# TNY-Test.net
KiCad netlist of a schematic drawn in EAGLE
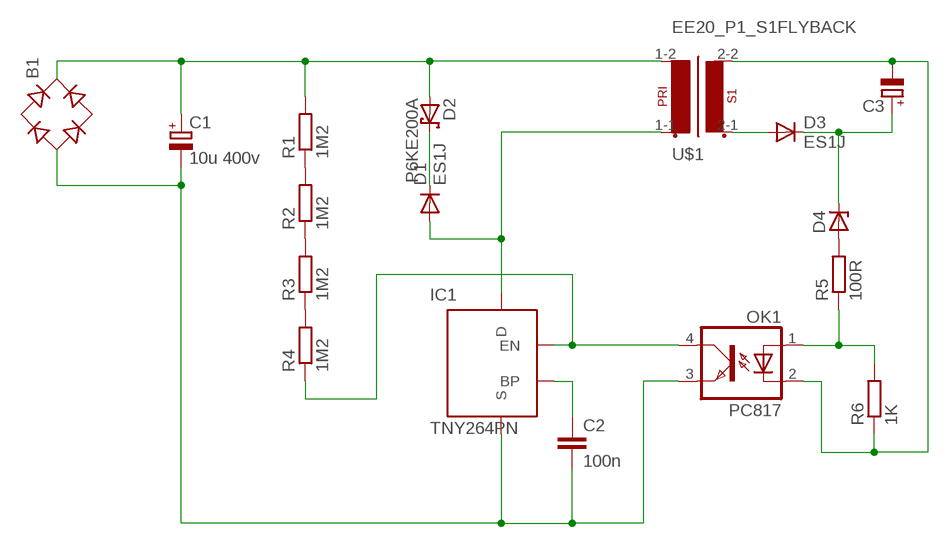
[diagram p0: schematic, sheet 1]

(export (version "E")
  (design (tool "Eeschema 10.0.6"))
  (components
    (comp (ref "B1")
      (value "RB1A")
      (footprint "eagle-import:RB1A")
      (libsource (lib "eagle-import") (part "RB1A"))
    )
    (comp (ref "C1")
      (value "10u 400v")
      (footprint "eagle-import:E5-13")
      (libsource (lib "eagle-import") (part "CPOL-EUE5-13"))
    )
    (comp (ref "C2")
      (value "100n")
      (footprint "eagle-import:C0805")
      (libsource (lib "eagle-import") (part "C-EUC0805"))
    )
    (comp (ref "C3")
      (value "CPOL-EUE2.5-7")
      (footprint "eagle-import:E2,5-7")
      (libsource (lib "eagle-import") (part "CPOL-EUE2.5-7"))
    )
    (comp (ref "D1")
      (value "ES1J")
      (footprint "eagle-import:DO214AC")
      (libsource (lib "eagle-import") (part "DIODE-DO214AC"))
    )
    (comp (ref "D2")
      (value "P6KE200A")
      (footprint "eagle-import:CB417-15")
      (libsource (lib "eagle-import") (part "P6KEXX"))
    )
    (comp (ref "D3")
      (value "ES1J")
      (footprint "eagle-import:DO214AC")
      (libsource (lib "eagle-import") (part "DIODE-DO214AC"))
    )
    (comp (ref "D4")
      (value "ZENER-DIODEDO41Z10")
      (footprint "eagle-import:DO41Z10")
      (libsource (lib "eagle-import") (part "ZENER-DIODEDO41Z10"))
    )
    (comp (ref "IC1")
      (value "TNY264PN")
      (footprint "eagle-import:DIP-8B")
      (libsource (lib "eagle-import") (part "TNY264PN"))
    )
    (comp (ref "OK1")
      (value "PC817")
      (footprint "eagle-import:DIL04")
      (fields (field (name "MPN") "PC817X4J000F"))
      (libsource (lib "eagle-import") (part "PC817"))
    )
    (comp (ref "R1")
      (value "1M2")
      (footprint "eagle-import:R0805")
      (libsource (lib "eagle-import") (part "R-EU_R0805"))
    )
    (comp (ref "R2")
      (value "1M2")
      (footprint "eagle-import:R0805")
      (libsource (lib "eagle-import") (part "R-EU_R0805"))
    )
    (comp (ref "R3")
      (value "1M2")
      (footprint "eagle-import:R0805")
      (libsource (lib "eagle-import") (part "R-EU_R0805"))
    )
    (comp (ref "R4")
      (value "1M2")
      (footprint "eagle-import:R0805")
      (libsource (lib "eagle-import") (part "R-EU_R0805"))
    )
    (comp (ref "R5")
      (value "100R")
      (footprint "eagle-import:R0805")
      (libsource (lib "eagle-import") (part "R-EU_R0805"))
    )
    (comp (ref "R6")
      (value "1K")
      (footprint "eagle-import:R0805")
      (libsource (lib "eagle-import") (part "R-EU_R0805"))
    )
    (comp (ref "U$1")
      (value "EE20_P1_S1FLYBACK")
      (footprint "eagle-import:EE20_P1_S1-REV-4PIN")
      (libsource (lib "eagle-import") (part "EE20_P1_S1FLYBACK"))
    )
  )
  (nets
    (net (code "1") (name "Net-(C3-Pad+)") (class "Default")
      (node (ref "C3") (pin "+") (pinfunction "+_+") (pintype "passive"))
      (node (ref "D3") (pin "C") (pinfunction "C_C") (pintype "passive"))
      (node (ref "D4") (pin "C") (pinfunction "C_C") (pintype "passive"))
    )
    (net (code "2") (name "Net-(D1-PadC)") (class "Default")
      (node (ref "D1") (pin "C") (pinfunction "C_C") (pintype "passive"))
      (node (ref "D2") (pin "C") (pinfunction "C_C") (pintype "passive"))
    )
    (net (code "3") (name "Net-(D4-PadA)") (class "Default")
      (node (ref "D4") (pin "A") (pinfunction "A_A") (pintype "passive"))
      (node (ref "R5") (pin "2") (pinfunction "2_2") (pintype "passive"))
    )
    (net (code "4") (name "Net-(IC1-BP)") (class "Default")
      (node (ref "C2") (pin "1") (pinfunction "1_1") (pintype "passive"))
      (node (ref "IC1") (pin "1") (pinfunction "BP_1") (pintype "input"))
    )
    (net (code "5") (name "Net-(IC1-D)") (class "Default")
      (node (ref "D1") (pin "A") (pinfunction "A_A") (pintype "passive"))
      (node (ref "IC1") (pin "5") (pinfunction "D_5") (pintype "input"))
      (node (ref "U$1") (pin "1-1") (pinfunction "P1-1_1-1") (pintype "passive"))
    )
    (net (code "6") (name "Net-(IC1-EN)") (class "Default")
      (node (ref "IC1") (pin "4") (pinfunction "EN_4") (pintype "input"))
      (node (ref "OK1") (pin "4") (pinfunction "COL_4") (pintype "passive"))
      (node (ref "R4") (pin "1") (pinfunction "1_1") (pintype "passive"))
    )
    (net (code "7") (name "Net-(OK1-A)") (class "Default")
      (node (ref "OK1") (pin "1") (pinfunction "A_1") (pintype "passive"))
      (node (ref "R5") (pin "1") (pinfunction "1_1") (pintype "passive"))
      (node (ref "R6") (pin "2") (pinfunction "2_2") (pintype "passive"))
    )
    (net (code "8") (name "Net-(OK1-C)") (class "Default")
      (node (ref "C3") (pin "-") (pinfunction "-_-") (pintype "passive"))
      (node (ref "OK1") (pin "2") (pinfunction "C_2") (pintype "passive"))
      (node (ref "R6") (pin "1") (pinfunction "1_1") (pintype "passive"))
      (node (ref "U$1") (pin "2-2") (pinfunction "S1-2_2-2") (pintype "passive"))
    )
    (net (code "9") (name "Net-(OK1-EMIT)") (class "Default")
      (node (ref "B1") (pin "-") (pinfunction "-_-") (pintype "passive"))
      (node (ref "C1") (pin "-") (pinfunction "-_-") (pintype "passive"))
      (node (ref "C2") (pin "2") (pinfunction "2_2") (pintype "passive"))
      (node (ref "IC1") (pin "2") (pinfunction "S_2") (pintype "input"))
      (node (ref "IC1") (pin "3") (pinfunction "S_3") (pintype "input"))
      (node (ref "IC1") (pin "7") (pinfunction "S_7") (pintype "input"))
      (node (ref "IC1") (pin "8") (pinfunction "S_8") (pintype "input"))
      (node (ref "OK1") (pin "3") (pinfunction "EMIT_3") (pintype "passive"))
    )
    (net (code "10") (name "Net-(R1-Pad1)") (class "Default")
      (node (ref "R1") (pin "1") (pinfunction "1_1") (pintype "passive"))
      (node (ref "R2") (pin "2") (pinfunction "2_2") (pintype "passive"))
    )
    (net (code "11") (name "Net-(R2-Pad1)") (class "Default")
      (node (ref "R2") (pin "1") (pinfunction "1_1") (pintype "passive"))
      (node (ref "R3") (pin "2") (pinfunction "2_2") (pintype "passive"))
    )
    (net (code "12") (name "Net-(R3-Pad1)") (class "Default")
      (node (ref "R3") (pin "1") (pinfunction "1_1") (pintype "passive"))
      (node (ref "R4") (pin "2") (pinfunction "2_2") (pintype "passive"))
    )
    (net (code "13") (name "Net-(U$1-P1-2)") (class "Default")
      (node (ref "B1") (pin "+") (pinfunction "+_+") (pintype "passive"))
      (node (ref "C1") (pin "+") (pinfunction "+_+") (pintype "passive"))
      (node (ref "D2") (pin "A") (pinfunction "A_A") (pintype "passive"))
      (node (ref "R1") (pin "2") (pinfunction "2_2") (pintype "passive"))
      (node (ref "U$1") (pin "1-2") (pinfunction "P1-2_1-2") (pintype "passive"))
    )
    (net (code "14") (name "Net-(U$1-S1-1)") (class "Default")
      (node (ref "D3") (pin "A") (pinfunction "A_A") (pintype "passive"))
      (node (ref "U$1") (pin "2-1") (pinfunction "S1-1_2-1") (pintype "passive"))
    )
    (net (code "15") (name "unconnected-(B1-PadAC1)") (class "Default")
      (node (ref "B1") (pin "AC1") (pinfunction "AC1_AC1") (pintype "passive"))
    )
    (net (code "16") (name "unconnected-(B1-PadAC2)") (class "Default")
      (node (ref "B1") (pin "AC2") (pinfunction "AC2_AC2") (pintype "passive"))
    )
  )
)
